# APP_1_DriveMoteur_m.net
KiCad netlist of a schematic drawn in Altium Designer
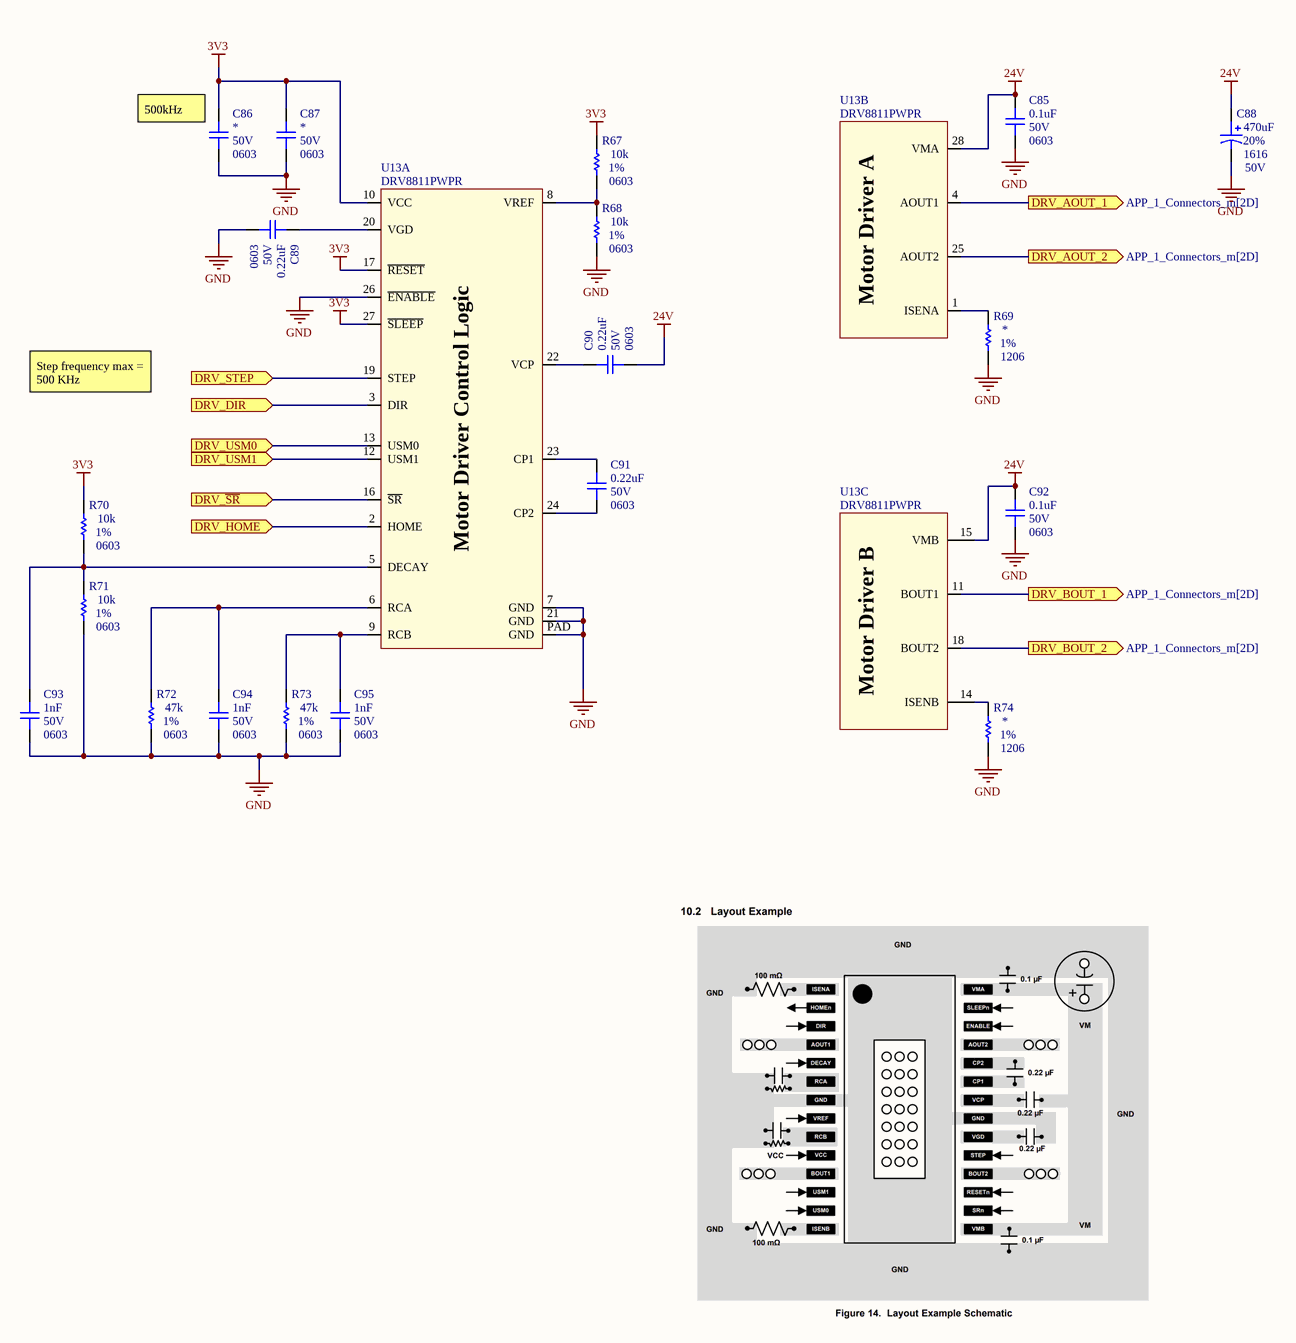
[diagram p0: APP_1_DriveMoteur_m.SchDoc]

(export (version "E")
  (design (tool "Eeschema 10.0.6"))
  (components
    (comp (ref "C85")
      (value "0.1uF")
      (footprint "CAP_0603")
      (description "CAP - 0603")
      (fields
        (field (name "VOLTAGE") "50V")
        (field (name "PACKAGE") "0603")
        (field (name "CREATEDBY") "Jonathan Bouchard")
      )
      (libsource (lib "S7CAS_LIB2023") (part "CAP - 0603"))
    )
    (comp (ref "C86")
      (value "CAP - 0603")
      (footprint "CAP_0603")
      (fields
        (field (name "VOLTAGE") "50V")
        (field (name "PACKAGE") "0603")
        (field (name "ALTIUM_VALUE") "*")
        (field (name "CREATEDBY") "Jonathan Bouchard")
      )
      (libsource (lib "S7CAS_LIB2023") (part "CAP - 0603"))
    )
    (comp (ref "C87")
      (value "CAP - 0603")
      (footprint "CAP_0603")
      (fields
        (field (name "VOLTAGE") "50V")
        (field (name "PACKAGE") "0603")
        (field (name "ALTIUM_VALUE") "*")
        (field (name "CREATEDBY") "Jonathan Bouchard")
      )
      (libsource (lib "S7CAS_LIB2023") (part "CAP - 0603"))
    )
    (comp (ref "C88")
      (value "470uF")
      (footprint "CAP_ALU_1616_vishay")
      (description "CAP - ALU 470uF 20% 50V - 1616")
      (fields
        (field (name "MFG") "Vishay Dale")
        (field (name "MFG PART NUMBER") "MAL214699108E3")
        (field (name "VOLTAGE") "50V")
        (field (name "PACKAGE") "1616")
        (field (name "PRECISION") "20%")
        (field (name "CREATEDBY") "Jonathan Bouchard")
      )
      (libsource (lib "S7CAS_LIB2023") (part "CAP_ALU_MAL214699108E3"))
    )
    (comp (ref "C89")
      (value "0.22uF")
      (footprint "CAP_0603")
      (description "CAP - 0603")
      (fields
        (field (name "VOLTAGE") "50V")
        (field (name "PACKAGE") "0603")
        (field (name "CREATEDBY") "Jonathan Bouchard")
      )
      (libsource (lib "S7CAS_LIB2023") (part "CAP - 0603"))
    )
    (comp (ref "C90")
      (value "0.22uF")
      (footprint "CAP_0603")
      (description "CAP - 0603")
      (fields
        (field (name "VOLTAGE") "50V")
        (field (name "PACKAGE") "0603")
        (field (name "CREATEDBY") "Jonathan Bouchard")
      )
      (libsource (lib "S7CAS_LIB2023") (part "CAP - 0603"))
    )
    (comp (ref "C91")
      (value "0.22uF")
      (footprint "CAP_0603")
      (description "CAP - 0603")
      (fields
        (field (name "VOLTAGE") "50V")
        (field (name "PACKAGE") "0603")
        (field (name "CREATEDBY") "Jonathan Bouchard")
      )
      (libsource (lib "S7CAS_LIB2023") (part "CAP - 0603"))
    )
    (comp (ref "C92")
      (value "0.1uF")
      (footprint "CAP_0603")
      (description "CAP - 0603")
      (fields
        (field (name "VOLTAGE") "50V")
        (field (name "PACKAGE") "0603")
        (field (name "CREATEDBY") "Jonathan Bouchard")
      )
      (libsource (lib "S7CAS_LIB2023") (part "CAP - 0603"))
    )
    (comp (ref "C93")
      (value "1nF")
      (footprint "CAP_0603")
      (description "CAP - 0603")
      (fields
        (field (name "VOLTAGE") "50V")
        (field (name "PACKAGE") "0603")
        (field (name "CREATEDBY") "Jonathan Bouchard")
      )
      (libsource (lib "S7CAS_LIB2023") (part "CAP - 0603"))
    )
    (comp (ref "C94")
      (value "1nF")
      (footprint "CAP_0603")
      (description "CAP - 0603")
      (fields
        (field (name "VOLTAGE") "50V")
        (field (name "PACKAGE") "0603")
        (field (name "CREATEDBY") "Jonathan Bouchard")
      )
      (libsource (lib "S7CAS_LIB2023") (part "CAP - 0603"))
    )
    (comp (ref "C95")
      (value "1nF")
      (footprint "CAP_0603")
      (description "CAP - 0603")
      (fields
        (field (name "VOLTAGE") "50V")
        (field (name "PACKAGE") "0603")
        (field (name "CREATEDBY") "Jonathan Bouchard")
      )
      (libsource (lib "S7CAS_LIB2023") (part "CAP - 0603"))
    )
    (comp (ref "R67")
      (value "10k")
      (footprint "RES_0603")
      (description "RES - 0603")
      (fields
        (field (name "PACKAGE") "0603")
        (field (name "PRECISION") "1%")
        (field (name "CREATEDBY") "Jonathan Bouchard")
      )
      (libsource (lib "S7CAS_LIB2023") (part "RES - 0603"))
    )
    (comp (ref "R68")
      (value "10k")
      (footprint "RES_0603")
      (description "RES - 0603")
      (fields
        (field (name "PACKAGE") "0603")
        (field (name "PRECISION") "1%")
        (field (name "CREATEDBY") "Jonathan Bouchard")
      )
      (libsource (lib "S7CAS_LIB2023") (part "RES - 0603"))
    )
    (comp (ref "R69")
      (value "RES - 1206")
      (footprint "RES_1206")
      (fields
        (field (name "PACKAGE") "1206")
        (field (name "PRECISION") "1%")
        (field (name "ALTIUM_VALUE") "*")
        (field (name "CREATEDBY") "Jonathan Bouchard")
      )
      (libsource (lib "S7CAS_LIB2023") (part "RES - 1206"))
    )
    (comp (ref "R70")
      (value "10k")
      (footprint "RES_0603")
      (description "RES - 0603")
      (fields
        (field (name "PACKAGE") "0603")
        (field (name "PRECISION") "1%")
        (field (name "CREATEDBY") "Jonathan Bouchard")
      )
      (libsource (lib "S7CAS_LIB2023") (part "RES - 0603"))
    )
    (comp (ref "R71")
      (value "10k")
      (footprint "RES_0603")
      (description "RES - 0603")
      (fields
        (field (name "PACKAGE") "0603")
        (field (name "PRECISION") "1%")
        (field (name "CREATEDBY") "Jonathan Bouchard")
      )
      (libsource (lib "S7CAS_LIB2023") (part "RES - 0603"))
    )
    (comp (ref "R72")
      (value "47k")
      (footprint "RES_0603")
      (description "RES - 0603")
      (fields
        (field (name "PACKAGE") "0603")
        (field (name "PRECISION") "1%")
        (field (name "CREATEDBY") "Jonathan Bouchard")
      )
      (libsource (lib "S7CAS_LIB2023") (part "RES - 0603"))
    )
    (comp (ref "R73")
      (value "47k")
      (footprint "RES_0603")
      (description "RES - 0603")
      (fields
        (field (name "PACKAGE") "0603")
        (field (name "PRECISION") "1%")
        (field (name "CREATEDBY") "Jonathan Bouchard")
      )
      (libsource (lib "S7CAS_LIB2023") (part "RES - 0603"))
    )
    (comp (ref "R74")
      (value "RES - 1206")
      (footprint "RES_1206")
      (fields
        (field (name "PACKAGE") "1206")
        (field (name "PRECISION") "1%")
        (field (name "ALTIUM_VALUE") "*")
        (field (name "CREATEDBY") "Jonathan Bouchard")
      )
      (libsource (lib "S7CAS_LIB2023") (part "RES - 1206"))
    )
    (comp (ref "U13")
      (value "DRV8811PWPR")
      (footprint "POW_MOTOR_DRV8811PWPR")
      (description "POW - STEPPER MOTOR DRIVER - SOP-28")
      (fields
        (field (name "VOLTAGE") "3 V ~ 5.5 V / 8 V ~ 38 V")
        (field (name "MFG") "Texas Instrument")
        (field (name "CREATEDBY") "Jonathan Bouchard")
      )
      (libsource (lib "S7CAS_LIB2023") (part "POW_MOTOR_DRV8811PWPR"))
    )
  )
  (nets
    (net (code "1") (name "/DRV_AOUT_1") (class "Default")
      (node (ref "U13") (pin "4") (pinfunction "AOUT1_4") (pintype "passive"))
    )
    (net (code "2") (name "/DRV_AOUT_2") (class "Default")
      (node (ref "U13") (pin "25") (pinfunction "AOUT2_25") (pintype "passive"))
    )
    (net (code "3") (name "/DRV_BOUT_1") (class "Default")
      (node (ref "U13") (pin "11") (pinfunction "BOUT1_11") (pintype "passive"))
    )
    (net (code "4") (name "/DRV_BOUT_2") (class "Default")
      (node (ref "U13") (pin "18") (pinfunction "BOUT2_18") (pintype "passive"))
    )
    (net (code "5") (name "/DRV_DIR") (class "Default")
      (node (ref "U13") (pin "3") (pinfunction "DIR_3") (pintype "passive"))
    )
    (net (code "6") (name "/DRV_HOME") (class "Default")
      (node (ref "U13") (pin "2") (pinfunction "HOME_2") (pintype "passive"))
    )
    (net (code "7") (name "/DRV_STEP") (class "Default")
      (node (ref "U13") (pin "19") (pinfunction "STEP_19") (pintype "passive"))
    )
    (net (code "8") (name "/DRV_USM0") (class "Default")
      (node (ref "U13") (pin "13") (pinfunction "USM0_13") (pintype "passive"))
    )
    (net (code "9") (name "/DRV_USM1") (class "Default")
      (node (ref "U13") (pin "12") (pinfunction "USM1_12") (pintype "passive"))
    )
    (net (code "10") (name "/DRV_~{SR}") (class "Default")
      (node (ref "U13") (pin "16") (pinfunction "~{SR}_16") (pintype "passive"))
    )
    (net (code "11") (name "3V3") (class "Default")
      (node (ref "C86") (pin "2") (pinfunction "2_2") (pintype "passive"))
      (node (ref "C87") (pin "2") (pinfunction "2_2") (pintype "passive"))
      (node (ref "R67") (pin "2") (pinfunction "2_2") (pintype "passive"))
      (node (ref "R70") (pin "2") (pinfunction "2_2") (pintype "passive"))
      (node (ref "U13") (pin "10") (pinfunction "VCC_10") (pintype "passive"))
      (node (ref "U13") (pin "17") (pinfunction "~{RESET}_17") (pintype "passive"))
      (node (ref "U13") (pin "27") (pinfunction "~{SLEEP}_27") (pintype "passive"))
    )
    (net (code "12") (name "24V") (class "Default")
      (node (ref "C85") (pin "2") (pinfunction "2_2") (pintype "passive"))
      (node (ref "C88") (pin "1") (pinfunction "1_1") (pintype "passive"))
      (node (ref "C90") (pin "1") (pinfunction "1_1") (pintype "passive"))
      (node (ref "C92") (pin "2") (pinfunction "2_2") (pintype "passive"))
      (node (ref "U13") (pin "15") (pinfunction "VMB_15") (pintype "passive"))
      (node (ref "U13") (pin "28") (pinfunction "VMA_28") (pintype "passive"))
    )
    (net (code "13") (name "GND") (class "Default")
      (node (ref "C85") (pin "1") (pinfunction "1_1") (pintype "passive"))
      (node (ref "C86") (pin "1") (pinfunction "1_1") (pintype "passive"))
      (node (ref "C87") (pin "1") (pinfunction "1_1") (pintype "passive"))
      (node (ref "C88") (pin "2") (pinfunction "2_2") (pintype "passive"))
      (node (ref "C89") (pin "1") (pinfunction "1_1") (pintype "passive"))
      (node (ref "C92") (pin "1") (pinfunction "1_1") (pintype "passive"))
      (node (ref "C93") (pin "1") (pinfunction "1_1") (pintype "passive"))
      (node (ref "C94") (pin "1") (pinfunction "1_1") (pintype "passive"))
      (node (ref "C95") (pin "1") (pinfunction "1_1") (pintype "passive"))
      (node (ref "R68") (pin "1") (pinfunction "1_1") (pintype "passive"))
      (node (ref "R69") (pin "1") (pinfunction "1_1") (pintype "passive"))
      (node (ref "R71") (pin "1") (pinfunction "1_1") (pintype "passive"))
      (node (ref "R72") (pin "1") (pinfunction "1_1") (pintype "passive"))
      (node (ref "R73") (pin "1") (pinfunction "1_1") (pintype "passive"))
      (node (ref "R74") (pin "1") (pinfunction "1_1") (pintype "passive"))
      (node (ref "U13") (pin "21") (pinfunction "GND_21") (pintype "passive"))
      (node (ref "U13") (pin "26") (pinfunction "~{ENABLE}_26") (pintype "passive"))
      (node (ref "U13") (pin "7") (pinfunction "GND_7") (pintype "passive"))
      (node (ref "U13") (pin "PAD") (pinfunction "GND_PAD") (pintype "passive"))
    )
    (net (code "14") (name "Net-(U13A-CP1)") (class "Default")
      (node (ref "C91") (pin "2") (pinfunction "2_2") (pintype "passive"))
      (node (ref "U13") (pin "23") (pinfunction "CP1_23") (pintype "passive"))
    )
    (net (code "15") (name "Net-(U13A-CP2)") (class "Default")
      (node (ref "C91") (pin "1") (pinfunction "1_1") (pintype "passive"))
      (node (ref "U13") (pin "24") (pinfunction "CP2_24") (pintype "passive"))
    )
    (net (code "16") (name "Net-(U13A-DECAY)") (class "Default")
      (node (ref "C93") (pin "2") (pinfunction "2_2") (pintype "passive"))
      (node (ref "R70") (pin "1") (pinfunction "1_1") (pintype "passive"))
      (node (ref "R71") (pin "2") (pinfunction "2_2") (pintype "passive"))
      (node (ref "U13") (pin "5") (pinfunction "DECAY_5") (pintype "passive"))
    )
    (net (code "17") (name "Net-(U13A-RCA)") (class "Default")
      (node (ref "C94") (pin "2") (pinfunction "2_2") (pintype "passive"))
      (node (ref "R72") (pin "2") (pinfunction "2_2") (pintype "passive"))
      (node (ref "U13") (pin "6") (pinfunction "RCA_6") (pintype "passive"))
    )
    (net (code "18") (name "Net-(U13A-RCB)") (class "Default")
      (node (ref "C95") (pin "2") (pinfunction "2_2") (pintype "passive"))
      (node (ref "R73") (pin "2") (pinfunction "2_2") (pintype "passive"))
      (node (ref "U13") (pin "9") (pinfunction "RCB_9") (pintype "passive"))
    )
    (net (code "19") (name "Net-(U13A-VCP)") (class "Default")
      (node (ref "C90") (pin "2") (pinfunction "2_2") (pintype "passive"))
      (node (ref "U13") (pin "22") (pinfunction "VCP_22") (pintype "passive"))
    )
    (net (code "20") (name "Net-(U13A-VGD)") (class "Default")
      (node (ref "C89") (pin "2") (pinfunction "2_2") (pintype "passive"))
      (node (ref "U13") (pin "20") (pinfunction "VGD_20") (pintype "passive"))
    )
    (net (code "21") (name "Net-(U13A-VREF)") (class "Default")
      (node (ref "R67") (pin "1") (pinfunction "1_1") (pintype "passive"))
      (node (ref "R68") (pin "2") (pinfunction "2_2") (pintype "passive"))
      (node (ref "U13") (pin "8") (pinfunction "VREF_8") (pintype "passive"))
    )
    (net (code "22") (name "Net-(U13B-ISENA)") (class "Default")
      (node (ref "R69") (pin "2") (pinfunction "2_2") (pintype "passive"))
      (node (ref "U13") (pin "1") (pinfunction "ISENA_1") (pintype "passive"))
    )
    (net (code "23") (name "Net-(U13C-ISENB)") (class "Default")
      (node (ref "R74") (pin "2") (pinfunction "2_2") (pintype "passive"))
      (node (ref "U13") (pin "14") (pinfunction "ISENB_14") (pintype "passive"))
    )
  )
)
